# circuito_distanciamento_social_ESP-01.net
KiCad netlist of a schematic drawn in EAGLE
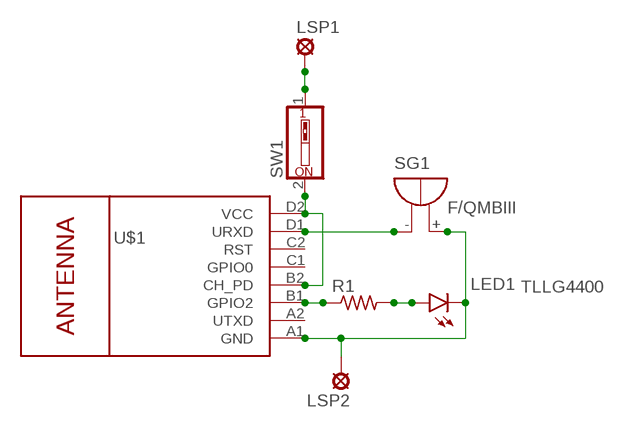
[diagram p0: schematic, sheet 1]

(export (version "E")
  (design (tool "Eeschema 10.0.6"))
  (components
    (comp (ref "LED1")
      (value "TLLG4400")
      (footprint "eagle-import:LED3MM")
      (fields (field (name "MF") "VISHAY SEMICONDUCTOR"))
      (libsource (lib "eagle-import") (part "TLLG4400"))
    )
    (comp (ref "LSP1")
      (value "LSP13")
      (footprint "eagle-import:LSP13")
      (libsource (lib "eagle-import") (part "LSP13"))
    )
    (comp (ref "LSP2")
      (value "LSP13")
      (footprint "eagle-import:LSP13")
      (libsource (lib "eagle-import") (part "LSP13"))
    )
    (comp (ref "R1")
      (value "R-US_0204/7")
      (footprint "eagle-import:0204_7")
      (libsource (lib "eagle-import") (part "R-US_0204/7"))
    )
    (comp (ref "SG1")
      (value "F/QMBIII")
      (footprint "eagle-import:F_QMBIII")
      (libsource (lib "eagle-import") (part "F/QMBIII"))
    )
    (comp (ref "SW1")
      (value "SW_DIP-1")
      (footprint "eagle-import:EDG-01")
      (libsource (lib "eagle-import") (part "SW_DIP-1"))
    )
    (comp (ref "U$1")
      (value "WIRELESS-WIFI-ESP-01")
      (footprint "eagle-import:WIRELESS-WIFI-ESP-01")
      (libsource (lib "eagle-import") (part "WIRELESS-WIFI-ESP-01"))
    )
  )
  (nets
    (net (code "1") (name "Net-(LED1-C)") (class "Default")
      (node (ref "LED1") (pin "K") (pinfunction "C_K") (pintype "passive"))
      (node (ref "LSP2") (pin "MP") (pinfunction "MP_MP") (pintype "passive"))
      (node (ref "SG1") (pin "+") (pinfunction "-_+") (pintype "passive"))
      (node (ref "U$1") (pin "A1") (pinfunction "GND_A1") (pintype "power_in"))
    )
    (net (code "2") (name "Net-(LED1-PadA)") (class "Default")
      (node (ref "LED1") (pin "A") (pinfunction "A_A") (pintype "passive"))
      (node (ref "R1") (pin "2") (pinfunction "2_2") (pintype "passive"))
    )
    (net (code "3") (name "Net-(LSP1-PadMP)") (class "Default")
      (node (ref "LSP1") (pin "MP") (pinfunction "MP_MP") (pintype "passive"))
      (node (ref "SW1") (pin "1") (pinfunction "1_1") (pintype "passive"))
    )
    (net (code "4") (name "Net-(SG1-+)") (class "Default")
      (node (ref "SG1") (pin "-") (pinfunction "+_-") (pintype "passive"))
      (node (ref "U$1") (pin "D1") (pinfunction "URXD_D1") (pintype "bidirectional"))
    )
    (net (code "5") (name "Net-(U$1-CH_PD)") (class "Default")
      (node (ref "SW1") (pin "2") (pinfunction "2_2") (pintype "passive"))
      (node (ref "U$1") (pin "B2") (pinfunction "CH_PD_B2") (pintype "bidirectional"))
      (node (ref "U$1") (pin "D2") (pinfunction "VCC_D2") (pintype "power_in"))
    )
    (net (code "6") (name "Net-(U$1-GPIO2)") (class "Default")
      (node (ref "R1") (pin "1") (pinfunction "1_1") (pintype "passive"))
      (node (ref "U$1") (pin "B1") (pinfunction "GPIO2_B1") (pintype "bidirectional"))
    )
    (net (code "7") (name "unconnected-(U$1-GPIO0-PadC1)") (class "Default")
      (node (ref "U$1") (pin "C1") (pinfunction "GPIO0_C1") (pintype "bidirectional"))
    )
    (net (code "8") (name "unconnected-(U$1-RST-PadC2)") (class "Default")
      (node (ref "U$1") (pin "C2") (pinfunction "RST_C2") (pintype "bidirectional"))
    )
    (net (code "9") (name "unconnected-(U$1-UTXD-PadA2)") (class "Default")
      (node (ref "U$1") (pin "A2") (pinfunction "UTXD_A2") (pintype "bidirectional"))
    )
  )
)
